# display.net
KiCad netlist of a schematic drawn in EAGLE
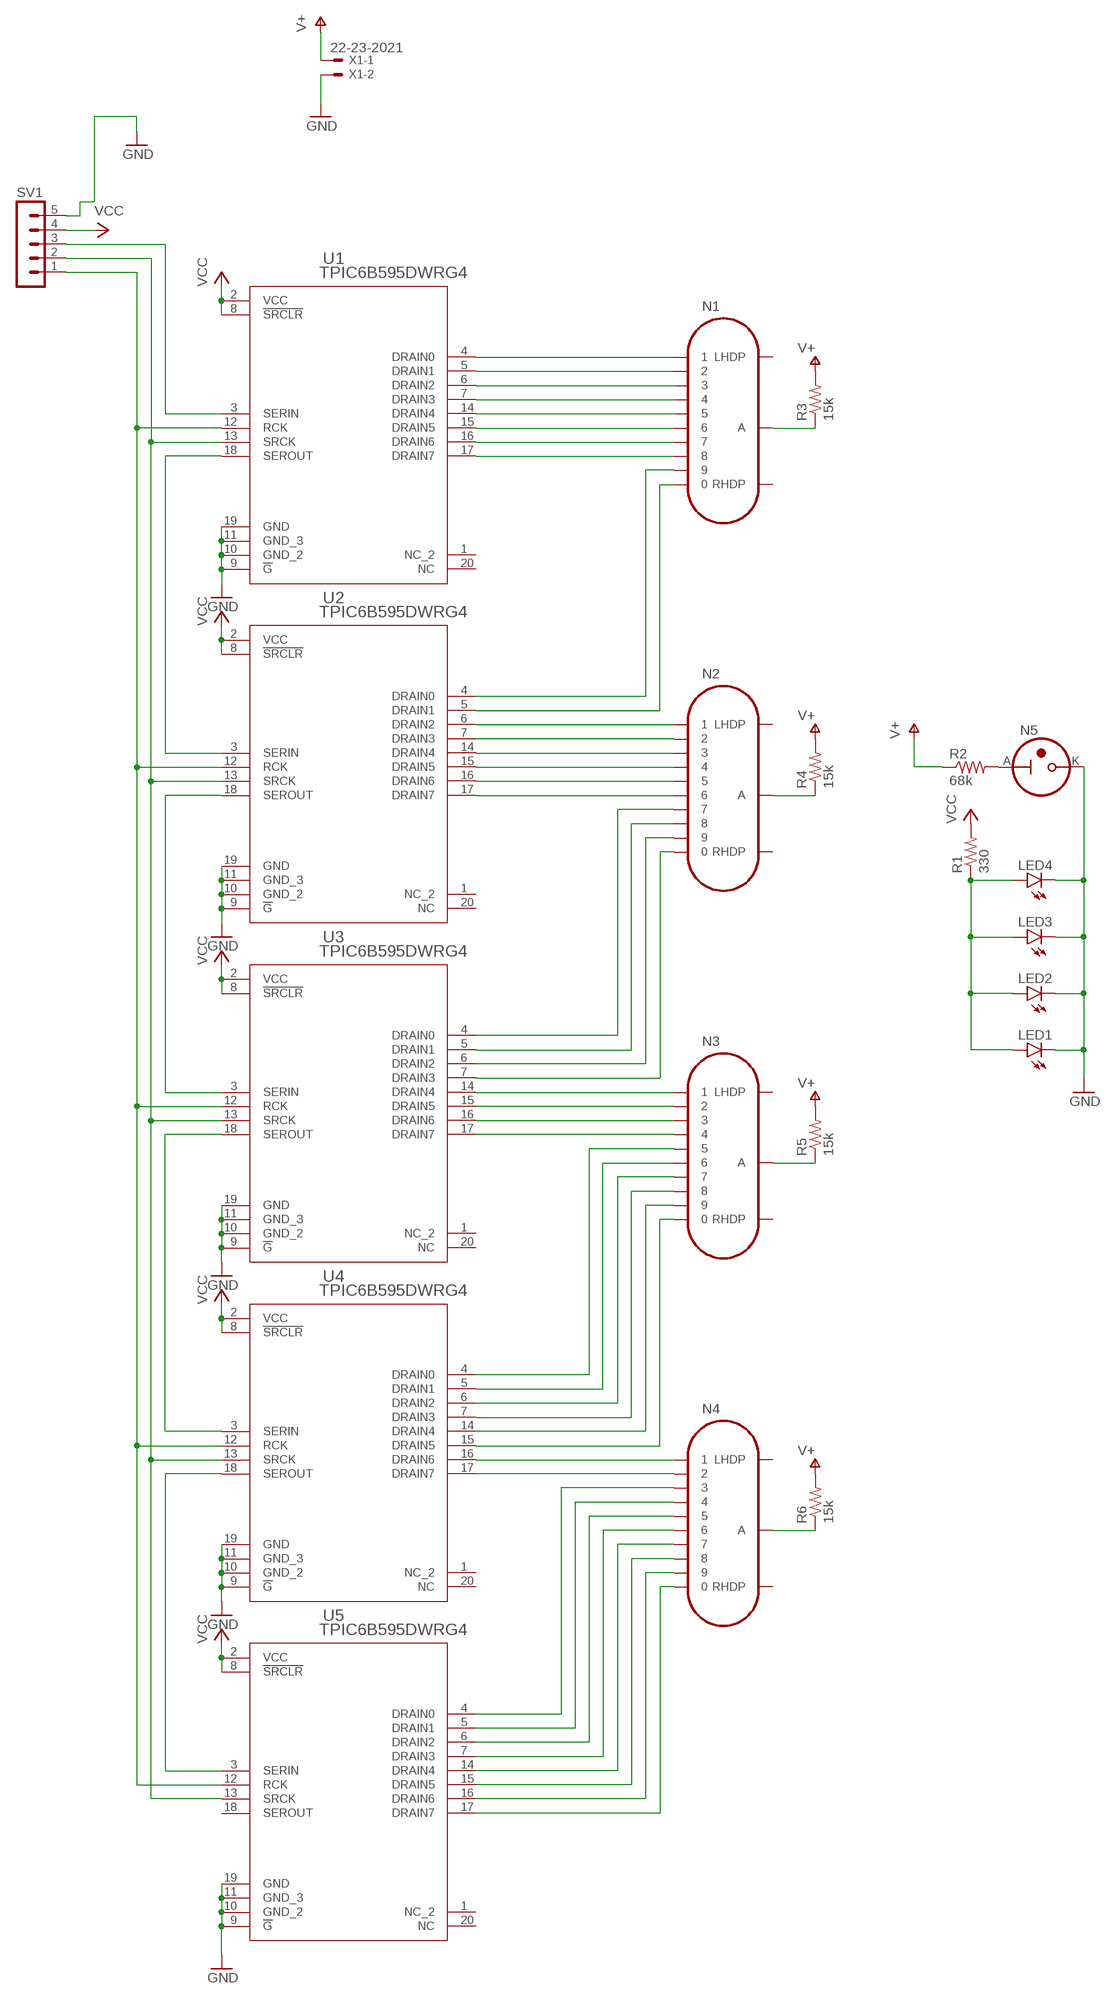
[diagram p0: schematic, sheet 1]

(export (version "E")
  (design (tool "Eeschema 10.0.6"))
  (components
    (comp (ref "LED1")
      (value "LED3MM")
      (footprint "eagle-import:LED3MM")
      (libsource (lib "eagle-import") (part "LED3MM"))
    )
    (comp (ref "LED2")
      (value "LED3MM")
      (footprint "eagle-import:LED3MM")
      (libsource (lib "eagle-import") (part "LED3MM"))
    )
    (comp (ref "LED3")
      (value "LED3MM")
      (footprint "eagle-import:LED3MM")
      (libsource (lib "eagle-import") (part "LED3MM"))
    )
    (comp (ref "LED4")
      (value "LED3MM")
      (footprint "eagle-import:LED3MM")
      (libsource (lib "eagle-import") (part "LED3MM"))
    )
    (comp (ref "N1")
      (value "IN-14")
      (footprint "eagle-import:IN-14")
      (libsource (lib "eagle-import") (part "IN-14"))
    )
    (comp (ref "N2")
      (value "IN-14")
      (footprint "eagle-import:IN-14")
      (libsource (lib "eagle-import") (part "IN-14"))
    )
    (comp (ref "N3")
      (value "IN-14")
      (footprint "eagle-import:IN-14")
      (libsource (lib "eagle-import") (part "IN-14"))
    )
    (comp (ref "N4")
      (value "IN-14")
      (footprint "eagle-import:IN-14")
      (libsource (lib "eagle-import") (part "IN-14"))
    )
    (comp (ref "N5")
      (value "IN-3")
      (footprint "eagle-import:IN-3")
      (libsource (lib "eagle-import") (part "IN-3"))
    )
    (comp (ref "R1")
      (value "330")
      (footprint "eagle-import:R0805")
      (libsource (lib "eagle-import") (part "R-US_R0805"))
    )
    (comp (ref "R2")
      (value "68k")
      (footprint "eagle-import:R0805")
      (libsource (lib "eagle-import") (part "R-US_R0805"))
    )
    (comp (ref "R3")
      (value "15k")
      (footprint "eagle-import:R0805")
      (libsource (lib "eagle-import") (part "R-US_R0805"))
    )
    (comp (ref "R4")
      (value "15k")
      (footprint "eagle-import:R0805")
      (libsource (lib "eagle-import") (part "R-US_R0805"))
    )
    (comp (ref "R5")
      (value "15k")
      (footprint "eagle-import:R0805")
      (libsource (lib "eagle-import") (part "R-US_R0805"))
    )
    (comp (ref "R6")
      (value "15k")
      (footprint "eagle-import:R0805")
      (libsource (lib "eagle-import") (part "R-US_R0805"))
    )
    (comp (ref "SV1")
      (value "MA05-1")
      (footprint "eagle-import:MA05-1")
      (libsource (lib "eagle-import") (part "MA05-1"))
    )
    (comp (ref "U1")
      (value "TPIC6B595DWRG4")
      (footprint "eagle-import:DW20")
      (fields (field (name "MANUFACTURER") "Texas Instruments"))
      (libsource (lib "eagle-import") (part "TPIC6B595DWRG4"))
    )
    (comp (ref "U2")
      (value "TPIC6B595DWRG4")
      (footprint "eagle-import:DW20")
      (fields (field (name "MANUFACTURER") "Texas Instruments"))
      (libsource (lib "eagle-import") (part "TPIC6B595DWRG4"))
    )
    (comp (ref "U3")
      (value "TPIC6B595DWRG4")
      (footprint "eagle-import:DW20")
      (fields (field (name "MANUFACTURER") "Texas Instruments"))
      (libsource (lib "eagle-import") (part "TPIC6B595DWRG4"))
    )
    (comp (ref "U4")
      (value "TPIC6B595DWRG4")
      (footprint "eagle-import:DW20")
      (fields (field (name "MANUFACTURER") "Texas Instruments"))
      (libsource (lib "eagle-import") (part "TPIC6B595DWRG4"))
    )
    (comp (ref "U5")
      (value "TPIC6B595DWRG4")
      (footprint "eagle-import:DW20")
      (fields (field (name "MANUFACTURER") "Texas Instruments"))
      (libsource (lib "eagle-import") (part "TPIC6B595DWRG4"))
    )
    (comp (ref "X1")
      (value "22-23-2021")
      (footprint "eagle-import:22-23-2021")
      (fields (field (name "MF") "MOLEX"))
      (libsource (lib "eagle-import") (part "22-23-2021"))
    )
  )
  (nets
    (net (code "1") (name "GND") (class "Default")
      (node (ref "LED1") (pin "K") (pinfunction "C_K") (pintype "passive"))
      (node (ref "LED2") (pin "K") (pinfunction "C_K") (pintype "passive"))
      (node (ref "LED3") (pin "K") (pinfunction "C_K") (pintype "passive"))
      (node (ref "LED4") (pin "K") (pinfunction "C_K") (pintype "passive"))
      (node (ref "N5") (pin "K") (pinfunction "K_K") (pintype "bidirectional"))
      (node (ref "SV1") (pin "5") (pinfunction "5_5") (pintype "passive"))
      (node (ref "U1") (pin "10") (pinfunction "GND_2_10") (pintype "power_in"))
      (node (ref "U1") (pin "11") (pinfunction "GND_3_11") (pintype "power_in"))
      (node (ref "U1") (pin "19") (pinfunction "GND_19") (pintype "power_in"))
      (node (ref "U1") (pin "9") (pinfunction "~{G}_9") (pintype "input"))
      (node (ref "U2") (pin "10") (pinfunction "GND_2_10") (pintype "power_in"))
      (node (ref "U2") (pin "11") (pinfunction "GND_3_11") (pintype "power_in"))
      (node (ref "U2") (pin "19") (pinfunction "GND_19") (pintype "power_in"))
      (node (ref "U2") (pin "9") (pinfunction "~{G}_9") (pintype "input"))
      (node (ref "U3") (pin "10") (pinfunction "GND_2_10") (pintype "power_in"))
      (node (ref "U3") (pin "11") (pinfunction "GND_3_11") (pintype "power_in"))
      (node (ref "U3") (pin "19") (pinfunction "GND_19") (pintype "power_in"))
      (node (ref "U3") (pin "9") (pinfunction "~{G}_9") (pintype "input"))
      (node (ref "U4") (pin "10") (pinfunction "GND_2_10") (pintype "power_in"))
      (node (ref "U4") (pin "11") (pinfunction "GND_3_11") (pintype "power_in"))
      (node (ref "U4") (pin "19") (pinfunction "GND_19") (pintype "power_in"))
      (node (ref "U4") (pin "9") (pinfunction "~{G}_9") (pintype "input"))
      (node (ref "U5") (pin "10") (pinfunction "GND_2_10") (pintype "power_in"))
      (node (ref "U5") (pin "11") (pinfunction "GND_3_11") (pintype "power_in"))
      (node (ref "U5") (pin "19") (pinfunction "GND_19") (pintype "power_in"))
      (node (ref "U5") (pin "9") (pinfunction "~{G}_9") (pintype "input"))
      (node (ref "X1") (pin "2") (pinfunction "S_2") (pintype "passive"))
    )
    (net (code "2") (name "Net-(LED1-PadA)") (class "Default")
      (node (ref "LED1") (pin "A") (pinfunction "A_A") (pintype "passive"))
      (node (ref "LED2") (pin "A") (pinfunction "A_A") (pintype "passive"))
      (node (ref "LED3") (pin "A") (pinfunction "A_A") (pintype "passive"))
      (node (ref "LED4") (pin "A") (pinfunction "A_A") (pintype "passive"))
      (node (ref "R1") (pin "1") (pinfunction "1_1") (pintype "passive"))
    )
    (net (code "3") (name "Net-(N1-PadA)") (class "Default")
      (node (ref "N1") (pin "A") (pinfunction "A_A") (pintype "bidirectional"))
      (node (ref "R3") (pin "1") (pinfunction "1_1") (pintype "passive"))
    )
    (net (code "4") (name "Net-(N2-PadA)") (class "Default")
      (node (ref "N2") (pin "A") (pinfunction "A_A") (pintype "bidirectional"))
      (node (ref "R4") (pin "1") (pinfunction "1_1") (pintype "passive"))
    )
    (net (code "5") (name "Net-(N3-PadA)") (class "Default")
      (node (ref "N3") (pin "A") (pinfunction "A_A") (pintype "bidirectional"))
      (node (ref "R5") (pin "1") (pinfunction "1_1") (pintype "passive"))
    )
    (net (code "6") (name "Net-(N4-PadA)") (class "Default")
      (node (ref "N4") (pin "A") (pinfunction "A_A") (pintype "bidirectional"))
      (node (ref "R6") (pin "1") (pinfunction "1_1") (pintype "passive"))
    )
    (net (code "7") (name "Net-(N5-PadA)") (class "Default")
      (node (ref "N5") (pin "A") (pinfunction "A_A") (pintype "bidirectional"))
      (node (ref "R2") (pin "2") (pinfunction "2_2") (pintype "passive"))
    )
    (net (code "8") (name "Net-(U1-DRAIN0)") (class "Default")
      (node (ref "N1") (pin "1") (pinfunction "1_1") (pintype "bidirectional"))
      (node (ref "U1") (pin "4") (pinfunction "DRAIN0_4") (pintype "output"))
    )
    (net (code "9") (name "Net-(U1-DRAIN1)") (class "Default")
      (node (ref "N1") (pin "2") (pinfunction "2_2") (pintype "bidirectional"))
      (node (ref "U1") (pin "5") (pinfunction "DRAIN1_5") (pintype "output"))
    )
    (net (code "10") (name "Net-(U1-DRAIN2)") (class "Default")
      (node (ref "N1") (pin "3") (pinfunction "3_3") (pintype "bidirectional"))
      (node (ref "U1") (pin "6") (pinfunction "DRAIN2_6") (pintype "output"))
    )
    (net (code "11") (name "Net-(U1-DRAIN3)") (class "Default")
      (node (ref "N1") (pin "4") (pinfunction "4_4") (pintype "bidirectional"))
      (node (ref "U1") (pin "7") (pinfunction "DRAIN3_7") (pintype "output"))
    )
    (net (code "12") (name "Net-(U1-DRAIN4)") (class "Default")
      (node (ref "N1") (pin "5") (pinfunction "5_5") (pintype "bidirectional"))
      (node (ref "U1") (pin "14") (pinfunction "DRAIN4_14") (pintype "output"))
    )
    (net (code "13") (name "Net-(U1-DRAIN5)") (class "Default")
      (node (ref "N1") (pin "6") (pinfunction "6_6") (pintype "bidirectional"))
      (node (ref "U1") (pin "15") (pinfunction "DRAIN5_15") (pintype "output"))
    )
    (net (code "14") (name "Net-(U1-DRAIN6)") (class "Default")
      (node (ref "N1") (pin "7") (pinfunction "7_7") (pintype "bidirectional"))
      (node (ref "U1") (pin "16") (pinfunction "DRAIN6_16") (pintype "output"))
    )
    (net (code "15") (name "Net-(U1-DRAIN7)") (class "Default")
      (node (ref "N1") (pin "8") (pinfunction "8_8") (pintype "bidirectional"))
      (node (ref "U1") (pin "17") (pinfunction "DRAIN7_17") (pintype "output"))
    )
    (net (code "16") (name "Net-(U1-RCK)") (class "Default")
      (node (ref "SV1") (pin "1") (pinfunction "1_1") (pintype "passive"))
      (node (ref "U1") (pin "12") (pinfunction "RCK_12") (pintype "input"))
      (node (ref "U2") (pin "12") (pinfunction "RCK_12") (pintype "input"))
      (node (ref "U3") (pin "12") (pinfunction "RCK_12") (pintype "input"))
      (node (ref "U4") (pin "12") (pinfunction "RCK_12") (pintype "input"))
      (node (ref "U5") (pin "12") (pinfunction "RCK_12") (pintype "input"))
    )
    (net (code "17") (name "Net-(U1-SERIN)") (class "Default")
      (node (ref "SV1") (pin "3") (pinfunction "3_3") (pintype "passive"))
      (node (ref "U1") (pin "3") (pinfunction "SERIN_3") (pintype "input"))
    )
    (net (code "18") (name "Net-(U1-SEROUT)") (class "Default")
      (node (ref "U1") (pin "18") (pinfunction "SEROUT_18") (pintype "output"))
      (node (ref "U2") (pin "3") (pinfunction "SERIN_3") (pintype "input"))
    )
    (net (code "19") (name "Net-(U1-SRCK)") (class "Default")
      (node (ref "SV1") (pin "2") (pinfunction "2_2") (pintype "passive"))
      (node (ref "U1") (pin "13") (pinfunction "SRCK_13") (pintype "input"))
      (node (ref "U2") (pin "13") (pinfunction "SRCK_13") (pintype "input"))
      (node (ref "U3") (pin "13") (pinfunction "SRCK_13") (pintype "input"))
      (node (ref "U4") (pin "13") (pinfunction "SRCK_13") (pintype "input"))
      (node (ref "U5") (pin "13") (pinfunction "SRCK_13") (pintype "input"))
    )
    (net (code "20") (name "Net-(U2-DRAIN0)") (class "Default")
      (node (ref "N1") (pin "9") (pinfunction "9_9") (pintype "bidirectional"))
      (node (ref "U2") (pin "4") (pinfunction "DRAIN0_4") (pintype "output"))
    )
    (net (code "21") (name "Net-(U2-DRAIN1)") (class "Default")
      (node (ref "N1") (pin "0") (pinfunction "0_0") (pintype "bidirectional"))
      (node (ref "U2") (pin "5") (pinfunction "DRAIN1_5") (pintype "output"))
    )
    (net (code "22") (name "Net-(U2-DRAIN2)") (class "Default")
      (node (ref "N2") (pin "1") (pinfunction "1_1") (pintype "bidirectional"))
      (node (ref "U2") (pin "6") (pinfunction "DRAIN2_6") (pintype "output"))
    )
    (net (code "23") (name "Net-(U2-DRAIN3)") (class "Default")
      (node (ref "N2") (pin "2") (pinfunction "2_2") (pintype "bidirectional"))
      (node (ref "U2") (pin "7") (pinfunction "DRAIN3_7") (pintype "output"))
    )
    (net (code "24") (name "Net-(U2-DRAIN4)") (class "Default")
      (node (ref "N2") (pin "3") (pinfunction "3_3") (pintype "bidirectional"))
      (node (ref "U2") (pin "14") (pinfunction "DRAIN4_14") (pintype "output"))
    )
    (net (code "25") (name "Net-(U2-DRAIN5)") (class "Default")
      (node (ref "N2") (pin "4") (pinfunction "4_4") (pintype "bidirectional"))
      (node (ref "U2") (pin "15") (pinfunction "DRAIN5_15") (pintype "output"))
    )
    (net (code "26") (name "Net-(U2-DRAIN6)") (class "Default")
      (node (ref "N2") (pin "5") (pinfunction "5_5") (pintype "bidirectional"))
      (node (ref "U2") (pin "16") (pinfunction "DRAIN6_16") (pintype "output"))
    )
    (net (code "27") (name "Net-(U2-DRAIN7)") (class "Default")
      (node (ref "N2") (pin "6") (pinfunction "6_6") (pintype "bidirectional"))
      (node (ref "U2") (pin "17") (pinfunction "DRAIN7_17") (pintype "output"))
    )
    (net (code "28") (name "Net-(U2-SEROUT)") (class "Default")
      (node (ref "U2") (pin "18") (pinfunction "SEROUT_18") (pintype "output"))
      (node (ref "U3") (pin "3") (pinfunction "SERIN_3") (pintype "input"))
    )
    (net (code "29") (name "Net-(U3-DRAIN0)") (class "Default")
      (node (ref "N2") (pin "7") (pinfunction "7_7") (pintype "bidirectional"))
      (node (ref "U3") (pin "4") (pinfunction "DRAIN0_4") (pintype "output"))
    )
    (net (code "30") (name "Net-(U3-DRAIN1)") (class "Default")
      (node (ref "N2") (pin "8") (pinfunction "8_8") (pintype "bidirectional"))
      (node (ref "U3") (pin "5") (pinfunction "DRAIN1_5") (pintype "output"))
    )
    (net (code "31") (name "Net-(U3-DRAIN2)") (class "Default")
      (node (ref "N2") (pin "9") (pinfunction "9_9") (pintype "bidirectional"))
      (node (ref "U3") (pin "6") (pinfunction "DRAIN2_6") (pintype "output"))
    )
    (net (code "32") (name "Net-(U3-DRAIN3)") (class "Default")
      (node (ref "N2") (pin "0") (pinfunction "0_0") (pintype "bidirectional"))
      (node (ref "U3") (pin "7") (pinfunction "DRAIN3_7") (pintype "output"))
    )
    (net (code "33") (name "Net-(U3-DRAIN4)") (class "Default")
      (node (ref "N3") (pin "1") (pinfunction "1_1") (pintype "bidirectional"))
      (node (ref "U3") (pin "14") (pinfunction "DRAIN4_14") (pintype "output"))
    )
    (net (code "34") (name "Net-(U3-DRAIN5)") (class "Default")
      (node (ref "N3") (pin "2") (pinfunction "2_2") (pintype "bidirectional"))
      (node (ref "U3") (pin "15") (pinfunction "DRAIN5_15") (pintype "output"))
    )
    (net (code "35") (name "Net-(U3-DRAIN6)") (class "Default")
      (node (ref "N3") (pin "3") (pinfunction "3_3") (pintype "bidirectional"))
      (node (ref "U3") (pin "16") (pinfunction "DRAIN6_16") (pintype "output"))
    )
    (net (code "36") (name "Net-(U3-DRAIN7)") (class "Default")
      (node (ref "N3") (pin "4") (pinfunction "4_4") (pintype "bidirectional"))
      (node (ref "U3") (pin "17") (pinfunction "DRAIN7_17") (pintype "output"))
    )
    (net (code "37") (name "Net-(U3-SEROUT)") (class "Default")
      (node (ref "U3") (pin "18") (pinfunction "SEROUT_18") (pintype "output"))
      (node (ref "U4") (pin "3") (pinfunction "SERIN_3") (pintype "input"))
    )
    (net (code "38") (name "Net-(U4-DRAIN0)") (class "Default")
      (node (ref "N3") (pin "5") (pinfunction "5_5") (pintype "bidirectional"))
      (node (ref "U4") (pin "4") (pinfunction "DRAIN0_4") (pintype "output"))
    )
    (net (code "39") (name "Net-(U4-DRAIN1)") (class "Default")
      (node (ref "N3") (pin "6") (pinfunction "6_6") (pintype "bidirectional"))
      (node (ref "U4") (pin "5") (pinfunction "DRAIN1_5") (pintype "output"))
    )
    (net (code "40") (name "Net-(U4-DRAIN2)") (class "Default")
      (node (ref "N3") (pin "7") (pinfunction "7_7") (pintype "bidirectional"))
      (node (ref "U4") (pin "6") (pinfunction "DRAIN2_6") (pintype "output"))
    )
    (net (code "41") (name "Net-(U4-DRAIN3)") (class "Default")
      (node (ref "N3") (pin "8") (pinfunction "8_8") (pintype "bidirectional"))
      (node (ref "U4") (pin "7") (pinfunction "DRAIN3_7") (pintype "output"))
    )
    (net (code "42") (name "Net-(U4-DRAIN4)") (class "Default")
      (node (ref "N3") (pin "9") (pinfunction "9_9") (pintype "bidirectional"))
      (node (ref "U4") (pin "14") (pinfunction "DRAIN4_14") (pintype "output"))
    )
    (net (code "43") (name "Net-(U4-DRAIN5)") (class "Default")
      (node (ref "N3") (pin "0") (pinfunction "0_0") (pintype "bidirectional"))
      (node (ref "U4") (pin "15") (pinfunction "DRAIN5_15") (pintype "output"))
    )
    (net (code "44") (name "Net-(U4-DRAIN6)") (class "Default")
      (node (ref "N4") (pin "1") (pinfunction "1_1") (pintype "bidirectional"))
      (node (ref "U4") (pin "16") (pinfunction "DRAIN6_16") (pintype "output"))
    )
    (net (code "45") (name "Net-(U4-DRAIN7)") (class "Default")
      (node (ref "N4") (pin "2") (pinfunction "2_2") (pintype "bidirectional"))
      (node (ref "U4") (pin "17") (pinfunction "DRAIN7_17") (pintype "output"))
    )
    (net (code "46") (name "Net-(U4-SEROUT)") (class "Default")
      (node (ref "U4") (pin "18") (pinfunction "SEROUT_18") (pintype "output"))
      (node (ref "U5") (pin "3") (pinfunction "SERIN_3") (pintype "input"))
    )
    (net (code "47") (name "Net-(U5-DRAIN0)") (class "Default")
      (node (ref "N4") (pin "3") (pinfunction "3_3") (pintype "bidirectional"))
      (node (ref "U5") (pin "4") (pinfunction "DRAIN0_4") (pintype "output"))
    )
    (net (code "48") (name "Net-(U5-DRAIN1)") (class "Default")
      (node (ref "N4") (pin "4") (pinfunction "4_4") (pintype "bidirectional"))
      (node (ref "U5") (pin "5") (pinfunction "DRAIN1_5") (pintype "output"))
    )
    (net (code "49") (name "Net-(U5-DRAIN2)") (class "Default")
      (node (ref "N4") (pin "5") (pinfunction "5_5") (pintype "bidirectional"))
      (node (ref "U5") (pin "6") (pinfunction "DRAIN2_6") (pintype "output"))
    )
    (net (code "50") (name "Net-(U5-DRAIN3)") (class "Default")
      (node (ref "N4") (pin "6") (pinfunction "6_6") (pintype "bidirectional"))
      (node (ref "U5") (pin "7") (pinfunction "DRAIN3_7") (pintype "output"))
    )
    (net (code "51") (name "Net-(U5-DRAIN4)") (class "Default")
      (node (ref "N4") (pin "7") (pinfunction "7_7") (pintype "bidirectional"))
      (node (ref "U5") (pin "14") (pinfunction "DRAIN4_14") (pintype "output"))
    )
    (net (code "52") (name "Net-(U5-DRAIN5)") (class "Default")
      (node (ref "N4") (pin "8") (pinfunction "8_8") (pintype "bidirectional"))
      (node (ref "U5") (pin "15") (pinfunction "DRAIN5_15") (pintype "output"))
    )
    (net (code "53") (name "Net-(U5-DRAIN6)") (class "Default")
      (node (ref "N4") (pin "9") (pinfunction "9_9") (pintype "bidirectional"))
      (node (ref "U5") (pin "16") (pinfunction "DRAIN6_16") (pintype "output"))
    )
    (net (code "54") (name "Net-(U5-DRAIN7)") (class "Default")
      (node (ref "N4") (pin "0") (pinfunction "0_0") (pintype "bidirectional"))
      (node (ref "U5") (pin "17") (pinfunction "DRAIN7_17") (pintype "output"))
    )
    (net (code "55") (name "V+") (class "Default")
      (node (ref "R2") (pin "1") (pinfunction "1_1") (pintype "passive"))
      (node (ref "R3") (pin "2") (pinfunction "2_2") (pintype "passive"))
      (node (ref "R4") (pin "2") (pinfunction "2_2") (pintype "passive"))
      (node (ref "R5") (pin "2") (pinfunction "2_2") (pintype "passive"))
      (node (ref "R6") (pin "2") (pinfunction "2_2") (pintype "passive"))
      (node (ref "X1") (pin "1") (pinfunction "S_1") (pintype "passive"))
    )
    (net (code "56") (name "VCC") (class "Default")
      (node (ref "R1") (pin "2") (pinfunction "2_2") (pintype "passive"))
      (node (ref "SV1") (pin "4") (pinfunction "4_4") (pintype "passive"))
      (node (ref "U1") (pin "2") (pinfunction "VCC_2") (pintype "power_in"))
      (node (ref "U1") (pin "8") (pinfunction "~{SRCLR}_8") (pintype "input"))
      (node (ref "U2") (pin "2") (pinfunction "VCC_2") (pintype "power_in"))
      (node (ref "U2") (pin "8") (pinfunction "~{SRCLR}_8") (pintype "input"))
      (node (ref "U3") (pin "2") (pinfunction "VCC_2") (pintype "power_in"))
      (node (ref "U3") (pin "8") (pinfunction "~{SRCLR}_8") (pintype "input"))
      (node (ref "U4") (pin "2") (pinfunction "VCC_2") (pintype "power_in"))
      (node (ref "U4") (pin "8") (pinfunction "~{SRCLR}_8") (pintype "input"))
      (node (ref "U5") (pin "2") (pinfunction "VCC_2") (pintype "power_in"))
      (node (ref "U5") (pin "8") (pinfunction "~{SRCLR}_8") (pintype "input"))
    )
    (net (code "57") (name "unconnected-(N1-PadLHDP)") (class "Default")
      (node (ref "N1") (pin "LHDP") (pinfunction "LHDP_LHDP") (pintype "bidirectional"))
    )
    (net (code "58") (name "unconnected-(N1-PadRHDP)") (class "Default")
      (node (ref "N1") (pin "RHDP") (pinfunction "RHDP_RHDP") (pintype "bidirectional"))
    )
    (net (code "59") (name "unconnected-(N2-PadLHDP)") (class "Default")
      (node (ref "N2") (pin "LHDP") (pinfunction "LHDP_LHDP") (pintype "bidirectional"))
    )
    (net (code "60") (name "unconnected-(N2-PadRHDP)") (class "Default")
      (node (ref "N2") (pin "RHDP") (pinfunction "RHDP_RHDP") (pintype "bidirectional"))
    )
    (net (code "61") (name "unconnected-(N3-PadLHDP)") (class "Default")
      (node (ref "N3") (pin "LHDP") (pinfunction "LHDP_LHDP") (pintype "bidirectional"))
    )
    (net (code "62") (name "unconnected-(N3-PadRHDP)") (class "Default")
      (node (ref "N3") (pin "RHDP") (pinfunction "RHDP_RHDP") (pintype "bidirectional"))
    )
    (net (code "63") (name "unconnected-(N4-PadLHDP)") (class "Default")
      (node (ref "N4") (pin "LHDP") (pinfunction "LHDP_LHDP") (pintype "bidirectional"))
    )
    (net (code "64") (name "unconnected-(N4-PadRHDP)") (class "Default")
      (node (ref "N4") (pin "RHDP") (pinfunction "RHDP_RHDP") (pintype "bidirectional"))
    )
    (net (code "65") (name "unconnected-(U1-NC-Pad20)") (class "Default")
      (node (ref "U1") (pin "20") (pinfunction "NC_20") (pintype "passive"))
    )
    (net (code "66") (name "unconnected-(U1-NC_2-Pad1)") (class "Default")
      (node (ref "U1") (pin "1") (pinfunction "NC_2_1") (pintype "passive"))
    )
    (net (code "67") (name "unconnected-(U2-NC-Pad20)") (class "Default")
      (node (ref "U2") (pin "20") (pinfunction "NC_20") (pintype "passive"))
    )
    (net (code "68") (name "unconnected-(U2-NC_2-Pad1)") (class "Default")
      (node (ref "U2") (pin "1") (pinfunction "NC_2_1") (pintype "passive"))
    )
    (net (code "69") (name "unconnected-(U3-NC-Pad20)") (class "Default")
      (node (ref "U3") (pin "20") (pinfunction "NC_20") (pintype "passive"))
    )
    (net (code "70") (name "unconnected-(U3-NC_2-Pad1)") (class "Default")
      (node (ref "U3") (pin "1") (pinfunction "NC_2_1") (pintype "passive"))
    )
    (net (code "71") (name "unconnected-(U4-NC-Pad20)") (class "Default")
      (node (ref "U4") (pin "20") (pinfunction "NC_20") (pintype "passive"))
    )
    (net (code "72") (name "unconnected-(U4-NC_2-Pad1)") (class "Default")
      (node (ref "U4") (pin "1") (pinfunction "NC_2_1") (pintype "passive"))
    )
    (net (code "73") (name "unconnected-(U5-NC-Pad20)") (class "Default")
      (node (ref "U5") (pin "20") (pinfunction "NC_20") (pintype "passive"))
    )
    (net (code "74") (name "unconnected-(U5-NC_2-Pad1)") (class "Default")
      (node (ref "U5") (pin "1") (pinfunction "NC_2_1") (pintype "passive"))
    )
    (net (code "75") (name "unconnected-(U5-SEROUT-Pad18)") (class "Default")
      (node (ref "U5") (pin "18") (pinfunction "SEROUT_18") (pintype "output"))
    )
  )
)
